# ESP32.net
KiCad netlist of a schematic drawn in Altium Designer
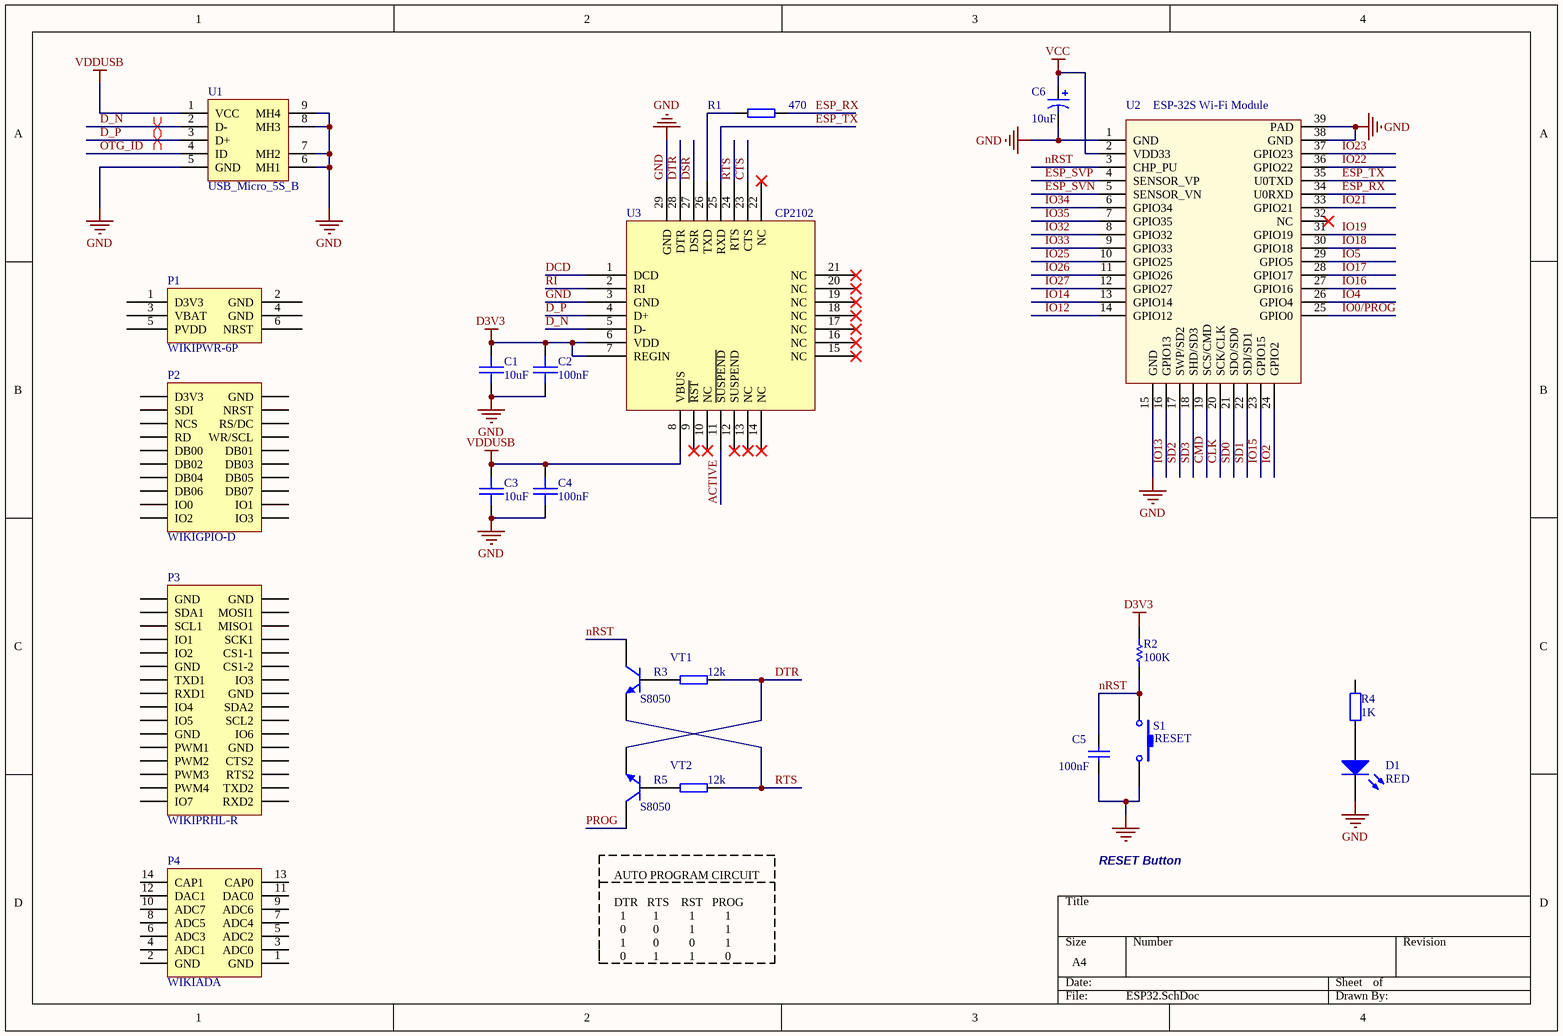
[diagram p0: ESP32.SchDoc]

(export (version "E")
  (design (tool "Eeschema 10.0.6"))
  (components
    (comp (ref "C1")
      (value "10uF")
      (footprint "C0603L")
      (description "Surface mount capacitor 0402")
      (libsource (lib "Vowstar_Basic_Device") (part "SMT_C_0402"))
    )
    (comp (ref "C2")
      (value "100nF")
      (footprint "C0603L")
      (description "Surface mount capacitor 0402")
      (libsource (lib "Vowstar_Basic_Device") (part "SMT_C_0402"))
    )
    (comp (ref "C3")
      (value "10uF")
      (footprint "C0603L")
      (description "Surface mount capacitor 0402")
      (libsource (lib "Vowstar_Basic_Device") (part "SMT_C_0402"))
    )
    (comp (ref "C4")
      (value "100nF")
      (footprint "C0603L")
      (description "Surface mount capacitor 0402")
      (libsource (lib "Vowstar_Basic_Device") (part "SMT_C_0402"))
    )
    (comp (ref "C5")
      (value "100nF")
      (footprint "C0603L")
      (description "Capacitor")
      (fields (field (name "PUBLISHER") "Altium Limited"))
      (libsource (lib "Miscellaneous Devices") (part "CAP"))
    )
    (comp (ref "C6")
      (value "10uF")
      (footprint "1210")
      (description "Polarized Capacitor (Axial)")
      (fields (field (name "PUBLISHER") "Altium Limited"))
      (libsource (lib "Misc") (part "Cap Pol2"))
    )
    (comp (ref "D1")
      (value "RED")
      (footprint "SMT_LED_0603")
      (description "Typical INFRARED GaAs LED")
      (fields (field (name "PUBLISHER") "Altium Limited"))
      (libsource (lib "Miscellaneous Devices") (part "LED0"))
    )
    (comp (ref "P1")
      (value "WIKIPWR-6P")
      (footprint "WIKIPWR-6P")
      (description "PWR HDR")
      (libsource (lib "Connector") (part "WIKIPWR-6P"))
    )
    (comp (ref "P2")
      (value "WIKIGPIO-D")
      (footprint "WIKIGPIO-U")
      (description "Header, 9-Pin, Dual row")
      (fields (field (name "PUBLISHER") "Altium Limited"))
      (libsource (lib "Connector") (part "WIKIGPIO-D"))
    )
    (comp (ref "P3")
      (value "WIKIPRHL-R")
      (footprint "WIKIPRHL-R")
      (description "Header, 16-Pin, Dual row")
      (fields (field (name "PUBLISHER") "Altium Limited"))
      (libsource (lib "Connector") (part "WIKIPRHL-R"))
    )
    (comp (ref "P4")
      (value "WIKIADA")
      (footprint "WIKIADA")
      (description "Header, 14-Pin, Dual row")
      (libsource (lib "Connector") (part "WIKIADA"))
    )
    (comp (ref "R1")
      (value "470")
      (footprint "R0603")
      (description "Surface mount resistor 0402")
      (libsource (lib "Vowstar_Basic_Device") (part "SMT_R_0402"))
    )
    (comp (ref "R2")
      (value "100K")
      (footprint "R0603")
      (description "Resistor")
      (fields (field (name "PUBLISHER") "Altium Limited"))
      (libsource (lib "Miscellaneous Devices") (part "res1"))
    )
    (comp (ref "R3")
      (value "12k")
      (footprint "R0603")
      (description "Surface mount resistor 0402")
      (libsource (lib "Vowstar_Basic_Device") (part "SMT_R_0402"))
    )
    (comp (ref "R4")
      (value "1K")
      (footprint "R0603")
      (description "Resistor")
      (fields (field (name "PUBLISHER") "Altium Limited"))
      (libsource (lib "Miscellaneous Devices") (part "Res2"))
    )
    (comp (ref "R5")
      (value "12k")
      (footprint "R0603")
      (description "Surface mount resistor 0402")
      (libsource (lib "Vowstar_Basic_Device") (part "SMT_R_0402"))
    )
    (comp (ref "S1")
      (value "RESET")
      (footprint "KEY-2x4-SMD")
      (description "Switch")
      (fields (field (name "PUBLISHER") "Altium Limited"))
      (libsource (lib "Miscellaneous Devices") (part "SW-PB"))
    )
    (comp (ref "U1")
      (value "USB_Micro_5S_B")
      (footprint "USB_MICRO_5S_B")
      (description "USB micro female SMT with 4 fixed foot")
      (libsource (lib "Vowstar_Connector") (part "USB_Micro_5S_B"))
    )
    (comp (ref "U2")
      (value "ESP-32S Wi-Fi Module")
      (footprint "ESP-32S")
      (libsource (lib "Module") (part "ESP-32S"))
    )
    (comp (ref "U3")
      (value "CP2102")
      (footprint "QFN28")
      (libsource (lib "Vowstar_IC_General") (part "CP2102"))
    )
    (comp (ref "VT1")
      (value "S8050")
      (footprint "SMT_TRIODE_NPN")
      (description "Surface mount NPN transistor, package SOT-23")
      (libsource (lib "Vowstar_Basic_Device") (part "SMT_TRIODE_NPN"))
    )
    (comp (ref "VT2")
      (value "S8050")
      (footprint "SMT_TRIODE_NPN")
      (description "Surface mount NPN transistor, package SOT-23")
      (libsource (lib "Vowstar_Basic_Device") (part "SMT_TRIODE_NPN"))
    )
  )
  (nets
    (net (code "1") (name "/ACTIVE") (class "Default")
      (node (ref "U3") (pin "11") (pinfunction "~{SUSPEND}_11") (pintype "passive"))
    )
    (net (code "2") (name "/CLK") (class "Default")
      (node (ref "U2") (pin "20") (pinfunction "SCK/CLK_20") (pintype "passive"))
    )
    (net (code "3") (name "/CMD") (class "Default")
      (node (ref "U2") (pin "19") (pinfunction "SCS/CMD_19") (pintype "passive"))
    )
    (net (code "4") (name "/CTS") (class "Default")
      (node (ref "U3") (pin "23") (pinfunction "CTS_23") (pintype "passive"))
    )
    (net (code "5") (name "/DCD") (class "Default")
      (node (ref "U3") (pin "1") (pinfunction "DCD_1") (pintype "passive"))
    )
    (net (code "6") (name "/DSR") (class "Default")
      (node (ref "U3") (pin "27") (pinfunction "DSR_27") (pintype "passive"))
    )
    (net (code "7") (name "/DTR") (class "Default")
      (node (ref "R3") (pin "2") (pinfunction "2_2") (pintype "passive"))
      (node (ref "U3") (pin "28") (pinfunction "DTR_28") (pintype "passive"))
      (node (ref "VT2") (pin "2") (pinfunction "E_2") (pintype "passive"))
    )
    (net (code "8") (name "/D_N") (class "Default")
      (node (ref "U1") (pin "2") (pinfunction "D-_2") (pintype "passive"))
      (node (ref "U3") (pin "5") (pinfunction "D-_5") (pintype "passive"))
    )
    (net (code "9") (name "/D_P") (class "Default")
      (node (ref "U1") (pin "3") (pinfunction "D+_3") (pintype "passive"))
      (node (ref "U3") (pin "4") (pinfunction "D+_4") (pintype "passive"))
    )
    (net (code "10") (name "/ESP_RX") (class "Default")
      (node (ref "R1") (pin "2") (pinfunction "2_2") (pintype "passive"))
      (node (ref "U2") (pin "34") (pinfunction "U0RXD_34") (pintype "passive"))
    )
    (net (code "11") (name "/ESP_SVN") (class "Default")
      (node (ref "U2") (pin "5") (pinfunction "SENSOR_VN_5") (pintype "passive"))
    )
    (net (code "12") (name "/ESP_SVP") (class "Default")
      (node (ref "U2") (pin "4") (pinfunction "SENSOR_VP_4") (pintype "passive"))
    )
    (net (code "13") (name "/ESP_TX") (class "Default")
      (node (ref "U2") (pin "35") (pinfunction "U0TXD_35") (pintype "passive"))
      (node (ref "U3") (pin "25") (pinfunction "RXD_25") (pintype "passive"))
    )
    (net (code "14") (name "/IO0{slash}PROG") (class "Default")
      (node (ref "U2") (pin "25") (pinfunction "GPIO0_25") (pintype "passive"))
    )
    (net (code "15") (name "/IO2") (class "Default")
      (node (ref "U2") (pin "24") (pinfunction "GPIO2_24") (pintype "passive"))
    )
    (net (code "16") (name "/IO4") (class "Default")
      (node (ref "U2") (pin "26") (pinfunction "GPIO4_26") (pintype "passive"))
    )
    (net (code "17") (name "/IO5") (class "Default")
      (node (ref "U2") (pin "29") (pinfunction "GPIO5_29") (pintype "passive"))
    )
    (net (code "18") (name "/IO12") (class "Default")
      (node (ref "U2") (pin "14") (pinfunction "GPIO12_14") (pintype "passive"))
    )
    (net (code "19") (name "/IO13") (class "Default")
      (node (ref "U2") (pin "16") (pinfunction "GPIO13_16") (pintype "passive"))
    )
    (net (code "20") (name "/IO14") (class "Default")
      (node (ref "U2") (pin "13") (pinfunction "GPIO14_13") (pintype "passive"))
    )
    (net (code "21") (name "/IO15") (class "Default")
      (node (ref "U2") (pin "23") (pinfunction "GPIO15_23") (pintype "passive"))
    )
    (net (code "22") (name "/IO16") (class "Default")
      (node (ref "U2") (pin "27") (pinfunction "GPIO16_27") (pintype "passive"))
    )
    (net (code "23") (name "/IO17") (class "Default")
      (node (ref "U2") (pin "28") (pinfunction "GPIO17_28") (pintype "passive"))
    )
    (net (code "24") (name "/IO18") (class "Default")
      (node (ref "U2") (pin "30") (pinfunction "GPIO18_30") (pintype "passive"))
    )
    (net (code "25") (name "/IO19") (class "Default")
      (node (ref "U2") (pin "31") (pinfunction "GPIO19_31") (pintype "passive"))
    )
    (net (code "26") (name "/IO21") (class "Default")
      (node (ref "U2") (pin "33") (pinfunction "GPIO21_33") (pintype "passive"))
    )
    (net (code "27") (name "/IO22") (class "Default")
      (node (ref "U2") (pin "36") (pinfunction "GPIO22_36") (pintype "passive"))
    )
    (net (code "28") (name "/IO23") (class "Default")
      (node (ref "U2") (pin "37") (pinfunction "GPIO23_37") (pintype "passive"))
    )
    (net (code "29") (name "/IO25") (class "Default")
      (node (ref "U2") (pin "10") (pinfunction "GPIO25_10") (pintype "passive"))
    )
    (net (code "30") (name "/IO26") (class "Default")
      (node (ref "U2") (pin "11") (pinfunction "GPIO26_11") (pintype "passive"))
    )
    (net (code "31") (name "/IO27") (class "Default")
      (node (ref "U2") (pin "12") (pinfunction "GPIO27_12") (pintype "passive"))
    )
    (net (code "32") (name "/IO32") (class "Default")
      (node (ref "U2") (pin "8") (pinfunction "GPIO32_8") (pintype "passive"))
    )
    (net (code "33") (name "/IO33") (class "Default")
      (node (ref "U2") (pin "9") (pinfunction "GPIO33_9") (pintype "passive"))
    )
    (net (code "34") (name "/IO34") (class "Default")
      (node (ref "U2") (pin "6") (pinfunction "GPIO34_6") (pintype "passive"))
    )
    (net (code "35") (name "/IO35") (class "Default")
      (node (ref "U2") (pin "7") (pinfunction "GPIO35_7") (pintype "passive"))
    )
    (net (code "36") (name "/OTG_ID") (class "Default")
      (node (ref "U1") (pin "4") (pinfunction "ID_4") (pintype "passive"))
    )
    (net (code "37") (name "/PROG") (class "Default")
      (node (ref "VT2") (pin "3") (pinfunction "C_3") (pintype "passive"))
    )
    (net (code "38") (name "/RI") (class "Default")
      (node (ref "U3") (pin "2") (pinfunction "RI_2") (pintype "passive"))
    )
    (net (code "39") (name "/RTS") (class "Default")
      (node (ref "R5") (pin "2") (pinfunction "2_2") (pintype "passive"))
      (node (ref "U3") (pin "24") (pinfunction "RTS_24") (pintype "passive"))
      (node (ref "VT1") (pin "2") (pinfunction "E_2") (pintype "passive"))
    )
    (net (code "40") (name "/SD0") (class "Default")
      (node (ref "U2") (pin "21") (pinfunction "SDO/SD0_21") (pintype "passive"))
    )
    (net (code "41") (name "/SD1") (class "Default")
      (node (ref "U2") (pin "22") (pinfunction "SDI/SD1_22") (pintype "passive"))
    )
    (net (code "42") (name "/SD2") (class "Default")
      (node (ref "U2") (pin "17") (pinfunction "SWP/SD2_17") (pintype "passive"))
    )
    (net (code "43") (name "/SD3") (class "Default")
      (node (ref "U2") (pin "18") (pinfunction "SHD/SD3_18") (pintype "passive"))
    )
    (net (code "44") (name "/nRST") (class "Default")
      (node (ref "C5") (pin "2") (pinfunction "2_2") (pintype "passive"))
      (node (ref "R2") (pin "1") (pinfunction "1_1") (pintype "passive"))
      (node (ref "S1") (pin "2") (pinfunction "2_2") (pintype "passive"))
      (node (ref "U2") (pin "3") (pinfunction "CHP_PU_3") (pintype "passive"))
      (node (ref "VT1") (pin "3") (pinfunction "C_3") (pintype "passive"))
    )
    (net (code "45") (name "D3V3") (class "Default")
      (node (ref "C1") (pin "1") (pinfunction "1_1") (pintype "passive"))
      (node (ref "C2") (pin "1") (pinfunction "1_1") (pintype "passive"))
      (node (ref "R2") (pin "2") (pinfunction "2_2") (pintype "passive"))
      (node (ref "U3") (pin "6") (pinfunction "VDD_6") (pintype "passive"))
      (node (ref "U3") (pin "7") (pinfunction "REGIN_7") (pintype "passive"))
    )
    (net (code "46") (name "GND") (class "Default")
      (node (ref "C1") (pin "2") (pinfunction "2_2") (pintype "passive"))
      (node (ref "C2") (pin "2") (pinfunction "2_2") (pintype "passive"))
      (node (ref "C3") (pin "2") (pinfunction "2_2") (pintype "passive"))
      (node (ref "C4") (pin "2") (pinfunction "2_2") (pintype "passive"))
      (node (ref "C5") (pin "1") (pinfunction "1_1") (pintype "passive"))
      (node (ref "C6") (pin "2") (pinfunction "2_2") (pintype "passive"))
      (node (ref "D1") (pin "2") (pinfunction "K_2") (pintype "passive"))
      (node (ref "S1") (pin "1") (pinfunction "1_1") (pintype "passive"))
      (node (ref "U1") (pin "5") (pinfunction "GND_5") (pintype "passive"))
      (node (ref "U1") (pin "6") (pinfunction "MH1_6") (pintype "passive"))
      (node (ref "U1") (pin "7") (pinfunction "MH2_7") (pintype "passive"))
      (node (ref "U1") (pin "8") (pinfunction "MH3_8") (pintype "passive"))
      (node (ref "U1") (pin "9") (pinfunction "MH4_9") (pintype "passive"))
      (node (ref "U2") (pin "1") (pinfunction "GND_1") (pintype "passive"))
      (node (ref "U2") (pin "15") (pinfunction "GND_15") (pintype "passive"))
      (node (ref "U2") (pin "38") (pinfunction "GND_38") (pintype "passive"))
      (node (ref "U2") (pin "39") (pinfunction "PAD_39") (pintype "passive"))
      (node (ref "U3") (pin "29") (pinfunction "GND_29") (pintype "passive"))
      (node (ref "U3") (pin "3") (pinfunction "GND_3") (pintype "passive"))
    )
    (net (code "47") (name "Net-(D1-A)") (class "Default")
      (node (ref "D1") (pin "1") (pinfunction "A_1") (pintype "passive"))
      (node (ref "R4") (pin "1") (pinfunction "1_1") (pintype "passive"))
    )
    (net (code "48") (name "Net-(U3-TXD)") (class "Default")
      (node (ref "R1") (pin "1") (pinfunction "1_1") (pintype "passive"))
      (node (ref "U3") (pin "26") (pinfunction "TXD_26") (pintype "passive"))
    )
    (net (code "49") (name "Net-(VT1-B)") (class "Default")
      (node (ref "R3") (pin "1") (pinfunction "1_1") (pintype "passive"))
      (node (ref "VT1") (pin "1") (pinfunction "B_1") (pintype "passive"))
    )
    (net (code "50") (name "Net-(VT2-B)") (class "Default")
      (node (ref "R5") (pin "1") (pinfunction "1_1") (pintype "passive"))
      (node (ref "VT2") (pin "1") (pinfunction "B_1") (pintype "passive"))
    )
    (net (code "51") (name "VCC") (class "Default")
      (node (ref "C6") (pin "1") (pinfunction "1_1") (pintype "passive"))
      (node (ref "U2") (pin "2") (pinfunction "VDD33_2") (pintype "passive"))
    )
    (net (code "52") (name "VDDUSB") (class "Default")
      (node (ref "C3") (pin "1") (pinfunction "1_1") (pintype "passive"))
      (node (ref "C4") (pin "1") (pinfunction "1_1") (pintype "passive"))
      (node (ref "U1") (pin "1") (pinfunction "VCC_1") (pintype "passive"))
      (node (ref "U3") (pin "8") (pinfunction "VBUS_8") (pintype "passive"))
    )
    (net (code "53") (name "unconnected-(P1-D3V3-Pad1)") (class "Default")
      (node (ref "P1") (pin "1") (pinfunction "D3V3_1") (pintype "passive"))
    )
    (net (code "54") (name "unconnected-(P1-GND-Pad2)") (class "Default")
      (node (ref "P1") (pin "2") (pinfunction "GND_2") (pintype "passive"))
    )
    (net (code "55") (name "unconnected-(P1-GND-Pad4)") (class "Default")
      (node (ref "P1") (pin "4") (pinfunction "GND_4") (pintype "passive"))
    )
    (net (code "56") (name "unconnected-(P1-NRST-Pad6)") (class "Default")
      (node (ref "P1") (pin "6") (pinfunction "NRST_6") (pintype "passive"))
    )
    (net (code "57") (name "unconnected-(P1-PVDD-Pad5)") (class "Default")
      (node (ref "P1") (pin "5") (pinfunction "PVDD_5") (pintype "passive"))
    )
    (net (code "58") (name "unconnected-(P1-VBAT-Pad3)") (class "Default")
      (node (ref "P1") (pin "3") (pinfunction "VBAT_3") (pintype "passive"))
    )
    (net (code "59") (name "unconnected-(P2-D3V3-Pad1)") (class "Default")
      (node (ref "P2") (pin "1") (pinfunction "D3V3_1") (pintype "passive"))
    )
    (net (code "60") (name "unconnected-(P2-DB00-Pad9)") (class "Default")
      (node (ref "P2") (pin "9") (pinfunction "DB00_9") (pintype "passive"))
    )
    (net (code "61") (name "unconnected-(P2-DB01-Pad10)") (class "Default")
      (node (ref "P2") (pin "10") (pinfunction "DB01_10") (pintype "passive"))
    )
    (net (code "62") (name "unconnected-(P2-DB02-Pad11)") (class "Default")
      (node (ref "P2") (pin "11") (pinfunction "DB02_11") (pintype "passive"))
    )
    (net (code "63") (name "unconnected-(P2-DB03-Pad12)") (class "Default")
      (node (ref "P2") (pin "12") (pinfunction "DB03_12") (pintype "passive"))
    )
    (net (code "64") (name "unconnected-(P2-DB04-Pad13)") (class "Default")
      (node (ref "P2") (pin "13") (pinfunction "DB04_13") (pintype "passive"))
    )
    (net (code "65") (name "unconnected-(P2-DB05-Pad14)") (class "Default")
      (node (ref "P2") (pin "14") (pinfunction "DB05_14") (pintype "passive"))
    )
    (net (code "66") (name "unconnected-(P2-DB06-Pad15)") (class "Default")
      (node (ref "P2") (pin "15") (pinfunction "DB06_15") (pintype "passive"))
    )
    (net (code "67") (name "unconnected-(P2-DB07-Pad16)") (class "Default")
      (node (ref "P2") (pin "16") (pinfunction "DB07_16") (pintype "passive"))
    )
    (net (code "68") (name "unconnected-(P2-GND-Pad2)") (class "Default")
      (node (ref "P2") (pin "2") (pinfunction "GND_2") (pintype "passive"))
    )
    (net (code "69") (name "unconnected-(P2-IO0-Pad17)") (class "Default")
      (node (ref "P2") (pin "17") (pinfunction "IO0_17") (pintype "passive"))
    )
    (net (code "70") (name "unconnected-(P2-IO1-Pad18)") (class "Default")
      (node (ref "P2") (pin "18") (pinfunction "IO1_18") (pintype "passive"))
    )
    (net (code "71") (name "unconnected-(P2-IO2-Pad19)") (class "Default")
      (node (ref "P2") (pin "19") (pinfunction "IO2_19") (pintype "passive"))
    )
    (net (code "72") (name "unconnected-(P2-IO3-Pad20)") (class "Default")
      (node (ref "P2") (pin "20") (pinfunction "IO3_20") (pintype "passive"))
    )
    (net (code "73") (name "unconnected-(P2-NCS-Pad5)") (class "Default")
      (node (ref "P2") (pin "5") (pinfunction "NCS_5") (pintype "passive"))
    )
    (net (code "74") (name "unconnected-(P2-NRST-Pad4)") (class "Default")
      (node (ref "P2") (pin "4") (pinfunction "NRST_4") (pintype "passive"))
    )
    (net (code "75") (name "unconnected-(P2-RD-Pad7)") (class "Default")
      (node (ref "P2") (pin "7") (pinfunction "RD_7") (pintype "passive"))
    )
    (net (code "76") (name "unconnected-(P2-RS{slash}DC-Pad6)") (class "Default")
      (node (ref "P2") (pin "6") (pinfunction "RS/DC_6") (pintype "passive"))
    )
    (net (code "77") (name "unconnected-(P2-SDI-Pad3)") (class "Default")
      (node (ref "P2") (pin "3") (pinfunction "SDI_3") (pintype "passive"))
    )
    (net (code "78") (name "unconnected-(P2-WR{slash}SCL-Pad8)") (class "Default")
      (node (ref "P2") (pin "8") (pinfunction "WR/SCL_8") (pintype "passive"))
    )
    (net (code "79") (name "unconnected-(P3-CS1-1-Pad10)") (class "Default")
      (node (ref "P3") (pin "10") (pinfunction "CS1-1_10") (pintype "passive"))
    )
    (net (code "80") (name "unconnected-(P3-CS1-2-Pad12)") (class "Default")
      (node (ref "P3") (pin "12") (pinfunction "CS1-2_12") (pintype "passive"))
    )
    (net (code "81") (name "unconnected-(P3-CTS2-Pad26)") (class "Default")
      (node (ref "P3") (pin "26") (pinfunction "CTS2_26") (pintype "passive"))
    )
    (net (code "82") (name "unconnected-(P3-GND-Pad1)") (class "Default")
      (node (ref "P3") (pin "1") (pinfunction "GND_1") (pintype "passive"))
    )
    (net (code "83") (name "unconnected-(P3-GND-Pad2)") (class "Default")
      (node (ref "P3") (pin "2") (pinfunction "GND_2") (pintype "passive"))
    )
    (net (code "84") (name "unconnected-(P3-GND-Pad11)") (class "Default")
      (node (ref "P3") (pin "11") (pinfunction "GND_11") (pintype "passive"))
    )
    (net (code "85") (name "unconnected-(P3-GND-Pad16)") (class "Default")
      (node (ref "P3") (pin "16") (pinfunction "GND_16") (pintype "passive"))
    )
    (net (code "86") (name "unconnected-(P3-GND-Pad21)") (class "Default")
      (node (ref "P3") (pin "21") (pinfunction "GND_21") (pintype "passive"))
    )
    (net (code "87") (name "unconnected-(P3-GND-Pad24)") (class "Default")
      (node (ref "P3") (pin "24") (pinfunction "GND_24") (pintype "passive"))
    )
    (net (code "88") (name "unconnected-(P3-IO1-Pad7)") (class "Default")
      (node (ref "P3") (pin "7") (pinfunction "IO1_7") (pintype "passive"))
    )
    (net (code "89") (name "unconnected-(P3-IO2-Pad9)") (class "Default")
      (node (ref "P3") (pin "9") (pinfunction "IO2_9") (pintype "passive"))
    )
    (net (code "90") (name "unconnected-(P3-IO3-Pad14)") (class "Default")
      (node (ref "P3") (pin "14") (pinfunction "IO3_14") (pintype "passive"))
    )
    (net (code "91") (name "unconnected-(P3-IO4-Pad17)") (class "Default")
      (node (ref "P3") (pin "17") (pinfunction "IO4_17") (pintype "passive"))
    )
    (net (code "92") (name "unconnected-(P3-IO5-Pad19)") (class "Default")
      (node (ref "P3") (pin "19") (pinfunction "IO5_19") (pintype "passive"))
    )
    (net (code "93") (name "unconnected-(P3-IO6-Pad22)") (class "Default")
      (node (ref "P3") (pin "22") (pinfunction "IO6_22") (pintype "passive"))
    )
    (net (code "94") (name "unconnected-(P3-IO7-Pad31)") (class "Default")
      (node (ref "P3") (pin "31") (pinfunction "IO7_31") (pintype "passive"))
    )
    (net (code "95") (name "unconnected-(P3-MISO1-Pad6)") (class "Default")
      (node (ref "P3") (pin "6") (pinfunction "MISO1_6") (pintype "passive"))
    )
    (net (code "96") (name "unconnected-(P3-MOSI1-Pad4)") (class "Default")
      (node (ref "P3") (pin "4") (pinfunction "MOSI1_4") (pintype "passive"))
    )
    (net (code "97") (name "unconnected-(P3-PWM1-Pad23)") (class "Default")
      (node (ref "P3") (pin "23") (pinfunction "PWM1_23") (pintype "passive"))
    )
    (net (code "98") (name "unconnected-(P3-PWM2-Pad25)") (class "Default")
      (node (ref "P3") (pin "25") (pinfunction "PWM2_25") (pintype "passive"))
    )
    (net (code "99") (name "unconnected-(P3-PWM3-Pad27)") (class "Default")
      (node (ref "P3") (pin "27") (pinfunction "PWM3_27") (pintype "passive"))
    )
    (net (code "100") (name "unconnected-(P3-PWM4-Pad29)") (class "Default")
      (node (ref "P3") (pin "29") (pinfunction "PWM4_29") (pintype "passive"))
    )
    (net (code "101") (name "unconnected-(P3-RTS2-Pad28)") (class "Default")
      (node (ref "P3") (pin "28") (pinfunction "RTS2_28") (pintype "passive"))
    )
    (net (code "102") (name "unconnected-(P3-RXD1-Pad15)") (class "Default")
      (node (ref "P3") (pin "15") (pinfunction "RXD1_15") (pintype "passive"))
    )
    (net (code "103") (name "unconnected-(P3-RXD2-Pad32)") (class "Default")
      (node (ref "P3") (pin "32") (pinfunction "RXD2_32") (pintype "passive"))
    )
    (net (code "104") (name "unconnected-(P3-SCK1-Pad8)") (class "Default")
      (node (ref "P3") (pin "8") (pinfunction "SCK1_8") (pintype "passive"))
    )
    (net (code "105") (name "unconnected-(P3-SCL1-Pad5)") (class "Default")
      (node (ref "P3") (pin "5") (pinfunction "SCL1_5") (pintype "passive"))
    )
    (net (code "106") (name "unconnected-(P3-SCL2-Pad20)") (class "Default")
      (node (ref "P3") (pin "20") (pinfunction "SCL2_20") (pintype "passive"))
    )
    (net (code "107") (name "unconnected-(P3-SDA1-Pad3)") (class "Default")
      (node (ref "P3") (pin "3") (pinfunction "SDA1_3") (pintype "passive"))
    )
    (net (code "108") (name "unconnected-(P3-SDA2-Pad18)") (class "Default")
      (node (ref "P3") (pin "18") (pinfunction "SDA2_18") (pintype "passive"))
    )
    (net (code "109") (name "unconnected-(P3-TXD1-Pad13)") (class "Default")
      (node (ref "P3") (pin "13") (pinfunction "TXD1_13") (pintype "passive"))
    )
    (net (code "110") (name "unconnected-(P3-TXD2-Pad30)") (class "Default")
      (node (ref "P3") (pin "30") (pinfunction "TXD2_30") (pintype "passive"))
    )
    (net (code "111") (name "unconnected-(P4-ADC0-Pad3)") (class "Default")
      (node (ref "P4") (pin "3") (pinfunction "ADC0_3") (pintype "passive"))
    )
    (net (code "112") (name "unconnected-(P4-ADC1-Pad4)") (class "Default")
      (node (ref "P4") (pin "4") (pinfunction "ADC1_4") (pintype "passive"))
    )
    (net (code "113") (name "unconnected-(P4-ADC2-Pad5)") (class "Default")
      (node (ref "P4") (pin "5") (pinfunction "ADC2_5") (pintype "passive"))
    )
    (net (code "114") (name "unconnected-(P4-ADC3-Pad6)") (class "Default")
      (node (ref "P4") (pin "6") (pinfunction "ADC3_6") (pintype "passive"))
    )
    (net (code "115") (name "unconnected-(P4-ADC4-Pad7)") (class "Default")
      (node (ref "P4") (pin "7") (pinfunction "ADC4_7") (pintype "passive"))
    )
    (net (code "116") (name "unconnected-(P4-ADC5-Pad8)") (class "Default")
      (node (ref "P4") (pin "8") (pinfunction "ADC5_8") (pintype "passive"))
    )
    (net (code "117") (name "unconnected-(P4-ADC6-Pad9)") (class "Default")
      (node (ref "P4") (pin "9") (pinfunction "ADC6_9") (pintype "passive"))
    )
    (net (code "118") (name "unconnected-(P4-ADC7-Pad10)") (class "Default")
      (node (ref "P4") (pin "10") (pinfunction "ADC7_10") (pintype "passive"))
    )
    (net (code "119") (name "unconnected-(P4-CAP0-Pad13)") (class "Default")
      (node (ref "P4") (pin "13") (pinfunction "CAP0_13") (pintype "passive"))
    )
    (net (code "120") (name "unconnected-(P4-CAP1-Pad14)") (class "Default")
      (node (ref "P4") (pin "14") (pinfunction "CAP1_14") (pintype "passive"))
    )
    (net (code "121") (name "unconnected-(P4-DAC0-Pad11)") (class "Default")
      (node (ref "P4") (pin "11") (pinfunction "DAC0_11") (pintype "passive"))
    )
    (net (code "122") (name "unconnected-(P4-DAC1-Pad12)") (class "Default")
      (node (ref "P4") (pin "12") (pinfunction "DAC1_12") (pintype "passive"))
    )
    (net (code "123") (name "unconnected-(P4-GND-Pad1)") (class "Default")
      (node (ref "P4") (pin "1") (pinfunction "GND_1") (pintype "passive"))
    )
    (net (code "124") (name "unconnected-(P4-GND-Pad2)") (class "Default")
      (node (ref "P4") (pin "2") (pinfunction "GND_2") (pintype "passive"))
    )
    (net (code "125") (name "unconnected-(R4-Pad2)") (class "Default")
      (node (ref "R4") (pin "2") (pinfunction "2_2") (pintype "passive"))
    )
    (net (code "126") (name "unconnected-(U2-NC-Pad32)") (class "Default")
      (node (ref "U2") (pin "32") (pinfunction "NC_32") (pintype "passive+no_connect"))
    )
    (net (code "127") (name "unconnected-(U3-NC-Pad10)") (class "Default")
      (node (ref "U3") (pin "10") (pinfunction "NC_10") (pintype "passive+no_connect"))
    )
    (net (code "128") (name "unconnected-(U3-NC-Pad13)") (class "Default")
      (node (ref "U3") (pin "13") (pinfunction "NC_13") (pintype "passive+no_connect"))
    )
    (net (code "129") (name "unconnected-(U3-NC-Pad14)") (class "Default")
      (node (ref "U3") (pin "14") (pinfunction "NC_14") (pintype "passive+no_connect"))
    )
    (net (code "130") (name "unconnected-(U3-NC-Pad15)") (class "Default")
      (node (ref "U3") (pin "15") (pinfunction "NC_15") (pintype "passive+no_connect"))
    )
    (net (code "131") (name "unconnected-(U3-NC-Pad16)") (class "Default")
      (node (ref "U3") (pin "16") (pinfunction "NC_16") (pintype "passive+no_connect"))
    )
    (net (code "132") (name "unconnected-(U3-NC-Pad17)") (class "Default")
      (node (ref "U3") (pin "17") (pinfunction "NC_17") (pintype "passive+no_connect"))
    )
    (net (code "133") (name "unconnected-(U3-NC-Pad18)") (class "Default")
      (node (ref "U3") (pin "18") (pinfunction "NC_18") (pintype "passive+no_connect"))
    )
    (net (code "134") (name "unconnected-(U3-NC-Pad19)") (class "Default")
      (node (ref "U3") (pin "19") (pinfunction "NC_19") (pintype "passive+no_connect"))
    )
    (net (code "135") (name "unconnected-(U3-NC-Pad20)") (class "Default")
      (node (ref "U3") (pin "20") (pinfunction "NC_20") (pintype "passive+no_connect"))
    )
    (net (code "136") (name "unconnected-(U3-NC-Pad21)") (class "Default")
      (node (ref "U3") (pin "21") (pinfunction "NC_21") (pintype "passive+no_connect"))
    )
    (net (code "137") (name "unconnected-(U3-NC-Pad22)") (class "Default")
      (node (ref "U3") (pin "22") (pinfunction "NC_22") (pintype "passive+no_connect"))
    )
    (net (code "138") (name "unconnected-(U3-SUSPEND-Pad12)") (class "Default")
      (node (ref "U3") (pin "12") (pinfunction "SUSPEND_12") (pintype "passive+no_connect"))
    )
    (net (code "139") (name "unconnected-(U3-~{RST}-Pad9)") (class "Default")
      (node (ref "U3") (pin "9") (pinfunction "~{RST}_9") (pintype "passive+no_connect"))
    )
  )
)
